# Laser_Array_Temp_Low_BRD_V2_1.net
KiCad netlist of a schematic drawn in EAGLE
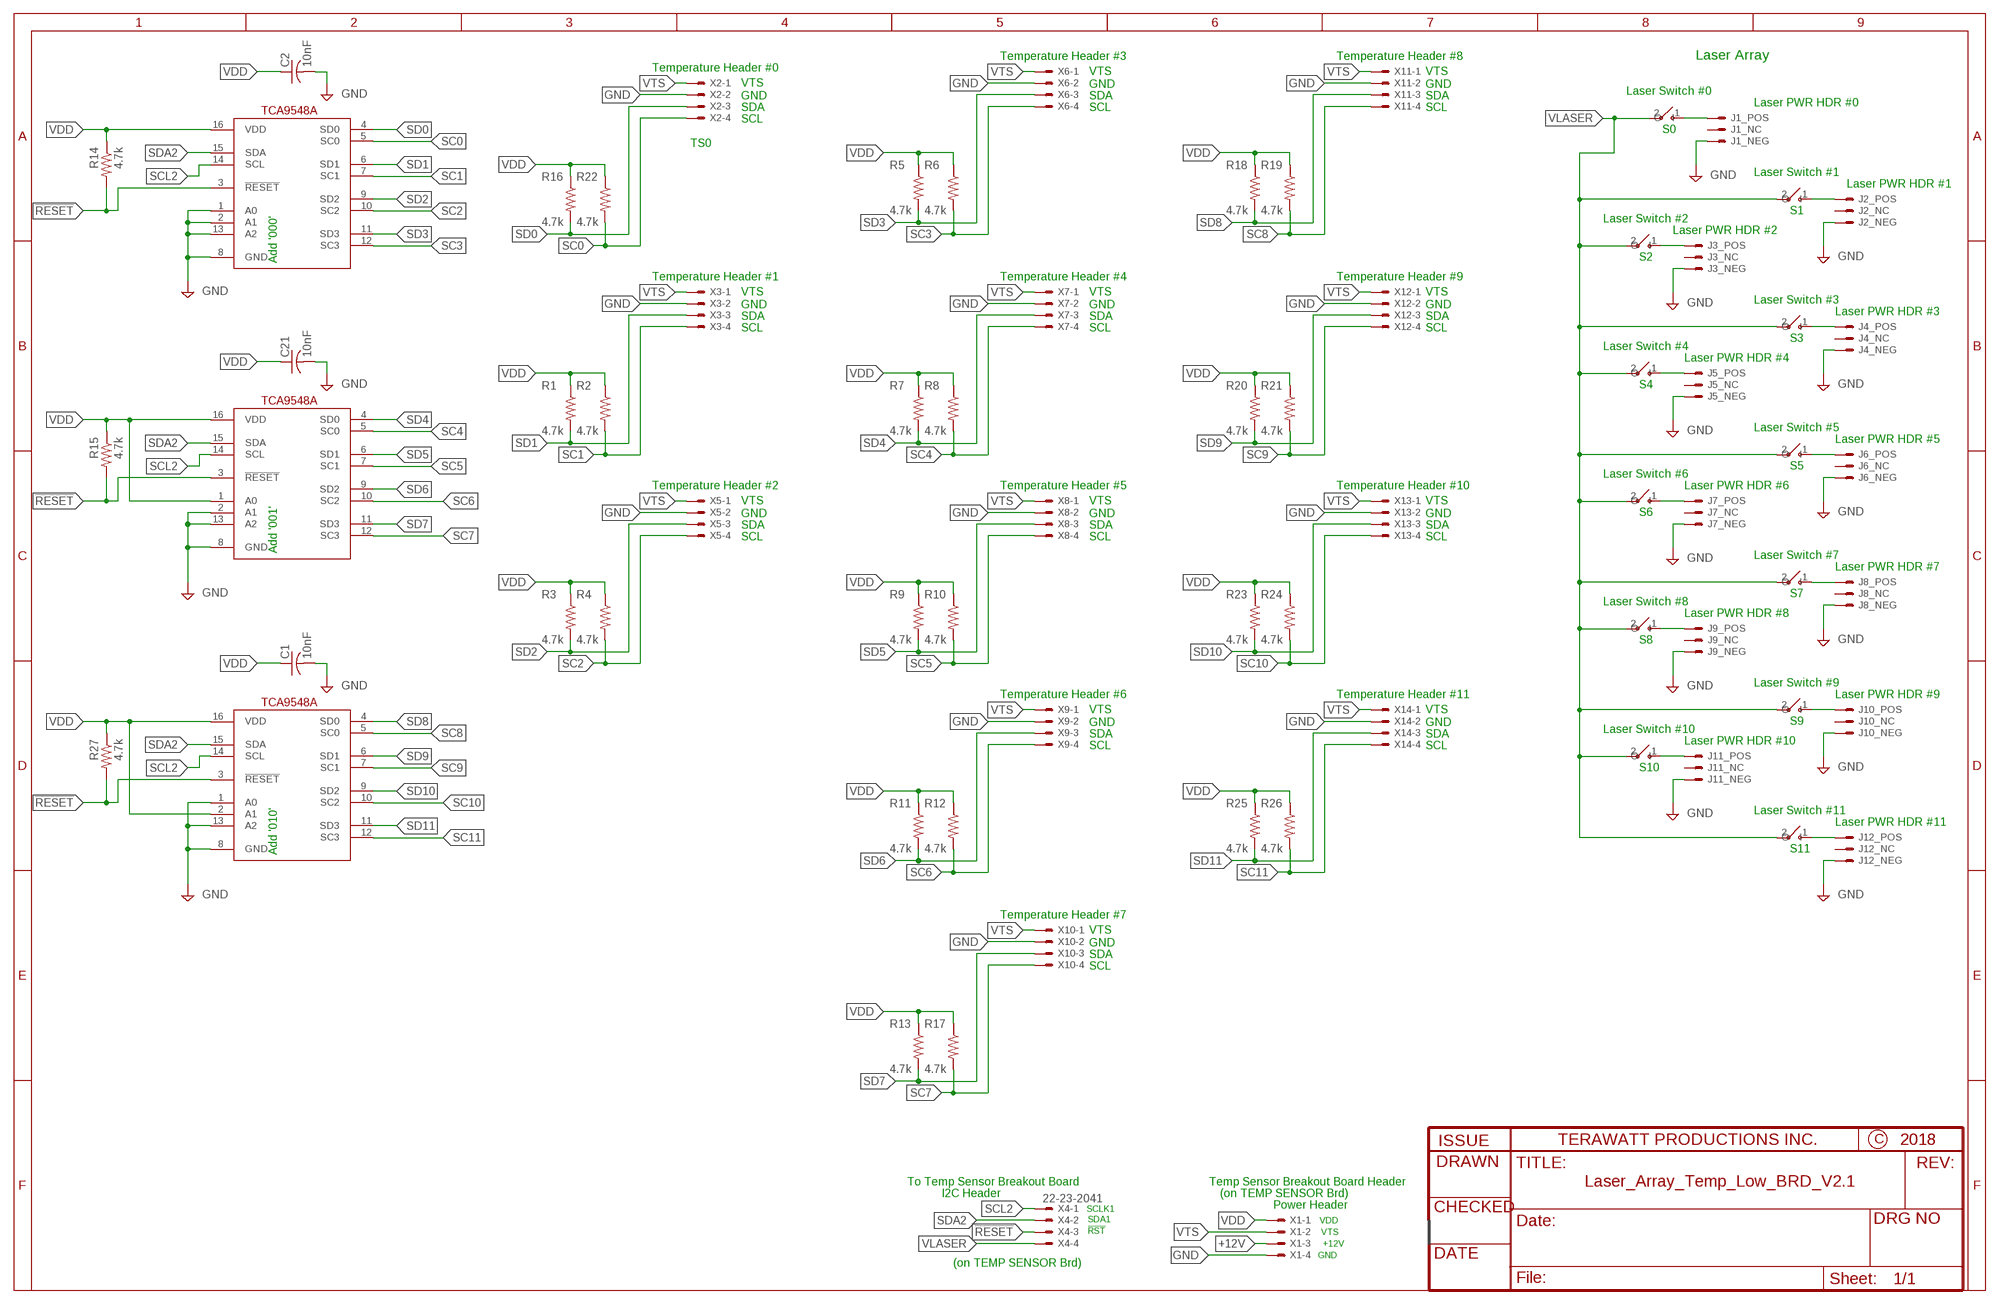
[diagram p0: schematic, sheet 1]

(export (version "E")
  (design (tool "Eeschema 10.0.6"))
  (components
    (comp (ref "C1")
      (value "10nF")
      (footprint "eagle-import:C0805")
      (libsource (lib "eagle-import") (part "C-USC0805"))
    )
    (comp (ref "C2")
      (value "10nF")
      (footprint "eagle-import:C0805")
      (libsource (lib "eagle-import") (part "C-USC0805"))
    )
    (comp (ref "C21")
      (value "10nF")
      (footprint "eagle-import:C0805")
      (libsource (lib "eagle-import") (part "C-USC0805"))
    )
    (comp (ref "J1")
      (value "LASER_MOD")
      (footprint "eagle-import:LASER_MOD")
      (libsource (lib "eagle-import") (part "LASER_MOD"))
    )
    (comp (ref "J2")
      (value "LASER_MOD")
      (footprint "eagle-import:LASER_MOD")
      (libsource (lib "eagle-import") (part "LASER_MOD"))
    )
    (comp (ref "J3")
      (value "LASER_MOD")
      (footprint "eagle-import:LASER_MOD")
      (libsource (lib "eagle-import") (part "LASER_MOD"))
    )
    (comp (ref "J4")
      (value "LASER_MOD")
      (footprint "eagle-import:LASER_MOD")
      (libsource (lib "eagle-import") (part "LASER_MOD"))
    )
    (comp (ref "J5")
      (value "LASER_MOD")
      (footprint "eagle-import:LASER_MOD")
      (libsource (lib "eagle-import") (part "LASER_MOD"))
    )
    (comp (ref "J6")
      (value "LASER_MOD")
      (footprint "eagle-import:LASER_MOD")
      (libsource (lib "eagle-import") (part "LASER_MOD"))
    )
    (comp (ref "J7")
      (value "LASER_MOD")
      (footprint "eagle-import:LASER_MOD")
      (libsource (lib "eagle-import") (part "LASER_MOD"))
    )
    (comp (ref "J8")
      (value "LASER_MOD")
      (footprint "eagle-import:LASER_MOD")
      (libsource (lib "eagle-import") (part "LASER_MOD"))
    )
    (comp (ref "J9")
      (value "LASER_MOD")
      (footprint "eagle-import:LASER_MOD")
      (libsource (lib "eagle-import") (part "LASER_MOD"))
    )
    (comp (ref "J10")
      (value "LASER_MOD")
      (footprint "eagle-import:LASER_MOD")
      (libsource (lib "eagle-import") (part "LASER_MOD"))
    )
    (comp (ref "J11")
      (value "LASER_MOD")
      (footprint "eagle-import:LASER_MOD")
      (libsource (lib "eagle-import") (part "LASER_MOD"))
    )
    (comp (ref "J12")
      (value "LASER_MOD")
      (footprint "eagle-import:LASER_MOD")
      (libsource (lib "eagle-import") (part "LASER_MOD"))
    )
    (comp (ref "R1")
      (value "4.7k")
      (footprint "eagle-import:M0805")
      (libsource (lib "eagle-import") (part "R-US_M0805"))
    )
    (comp (ref "R2")
      (value "4.7k")
      (footprint "eagle-import:M0805")
      (libsource (lib "eagle-import") (part "R-US_M0805"))
    )
    (comp (ref "R3")
      (value "4.7k")
      (footprint "eagle-import:M0805")
      (libsource (lib "eagle-import") (part "R-US_M0805"))
    )
    (comp (ref "R4")
      (value "4.7k")
      (footprint "eagle-import:M0805")
      (libsource (lib "eagle-import") (part "R-US_M0805"))
    )
    (comp (ref "R5")
      (value "4.7k")
      (footprint "eagle-import:M0805")
      (libsource (lib "eagle-import") (part "R-US_M0805"))
    )
    (comp (ref "R6")
      (value "4.7k")
      (footprint "eagle-import:M0805")
      (libsource (lib "eagle-import") (part "R-US_M0805"))
    )
    (comp (ref "R7")
      (value "4.7k")
      (footprint "eagle-import:M0805")
      (libsource (lib "eagle-import") (part "R-US_M0805"))
    )
    (comp (ref "R8")
      (value "4.7k")
      (footprint "eagle-import:M0805")
      (libsource (lib "eagle-import") (part "R-US_M0805"))
    )
    (comp (ref "R9")
      (value "4.7k")
      (footprint "eagle-import:M0805")
      (libsource (lib "eagle-import") (part "R-US_M0805"))
    )
    (comp (ref "R10")
      (value "4.7k")
      (footprint "eagle-import:M0805")
      (libsource (lib "eagle-import") (part "R-US_M0805"))
    )
    (comp (ref "R11")
      (value "4.7k")
      (footprint "eagle-import:M0805")
      (libsource (lib "eagle-import") (part "R-US_M0805"))
    )
    (comp (ref "R12")
      (value "4.7k")
      (footprint "eagle-import:M0805")
      (libsource (lib "eagle-import") (part "R-US_M0805"))
    )
    (comp (ref "R13")
      (value "4.7k")
      (footprint "eagle-import:M0805")
      (libsource (lib "eagle-import") (part "R-US_M0805"))
    )
    (comp (ref "R14")
      (value "4.7k")
      (footprint "eagle-import:M0805")
      (libsource (lib "eagle-import") (part "R-US_M0805"))
    )
    (comp (ref "R15")
      (value "4.7k")
      (footprint "eagle-import:M0805")
      (libsource (lib "eagle-import") (part "R-US_M0805"))
    )
    (comp (ref "R16")
      (value "4.7k")
      (footprint "eagle-import:M0805")
      (libsource (lib "eagle-import") (part "R-US_M0805"))
    )
    (comp (ref "R17")
      (value "4.7k")
      (footprint "eagle-import:M0805")
      (libsource (lib "eagle-import") (part "R-US_M0805"))
    )
    (comp (ref "R18")
      (value "4.7k")
      (footprint "eagle-import:M0805")
      (libsource (lib "eagle-import") (part "R-US_M0805"))
    )
    (comp (ref "R19")
      (value "4.7k")
      (footprint "eagle-import:M0805")
      (libsource (lib "eagle-import") (part "R-US_M0805"))
    )
    (comp (ref "R20")
      (value "4.7k")
      (footprint "eagle-import:M0805")
      (libsource (lib "eagle-import") (part "R-US_M0805"))
    )
    (comp (ref "R21")
      (value "4.7k")
      (footprint "eagle-import:M0805")
      (libsource (lib "eagle-import") (part "R-US_M0805"))
    )
    (comp (ref "R22")
      (value "4.7k")
      (footprint "eagle-import:M0805")
      (libsource (lib "eagle-import") (part "R-US_M0805"))
    )
    (comp (ref "R23")
      (value "4.7k")
      (footprint "eagle-import:M0805")
      (libsource (lib "eagle-import") (part "R-US_M0805"))
    )
    (comp (ref "R24")
      (value "4.7k")
      (footprint "eagle-import:M0805")
      (libsource (lib "eagle-import") (part "R-US_M0805"))
    )
    (comp (ref "R25")
      (value "4.7k")
      (footprint "eagle-import:M0805")
      (libsource (lib "eagle-import") (part "R-US_M0805"))
    )
    (comp (ref "R26")
      (value "4.7k")
      (footprint "eagle-import:M0805")
      (libsource (lib "eagle-import") (part "R-US_M0805"))
    )
    (comp (ref "R27")
      (value "4.7k")
      (footprint "eagle-import:M0805")
      (libsource (lib "eagle-import") (part "R-US_M0805"))
    )
    (comp (ref "S13")
      (value "TOGGLE_SPST")
      (footprint "eagle-import:22-23-2021")
      (libsource (lib "eagle-import") (part "TOGGLE_SPST"))
    )
    (comp (ref "S14")
      (value "TOGGLE_SPST")
      (footprint "eagle-import:22-23-2021")
      (libsource (lib "eagle-import") (part "TOGGLE_SPST"))
    )
    (comp (ref "S15")
      (value "TOGGLE_SPST")
      (footprint "eagle-import:22-23-2021")
      (libsource (lib "eagle-import") (part "TOGGLE_SPST"))
    )
    (comp (ref "S16")
      (value "TOGGLE_SPST")
      (footprint "eagle-import:22-23-2021")
      (libsource (lib "eagle-import") (part "TOGGLE_SPST"))
    )
    (comp (ref "S17")
      (value "TOGGLE_SPST")
      (footprint "eagle-import:22-23-2021")
      (libsource (lib "eagle-import") (part "TOGGLE_SPST"))
    )
    (comp (ref "S18")
      (value "TOGGLE_SPST")
      (footprint "eagle-import:22-23-2021")
      (libsource (lib "eagle-import") (part "TOGGLE_SPST"))
    )
    (comp (ref "S19")
      (value "TOGGLE_SPST")
      (footprint "eagle-import:22-23-2021")
      (libsource (lib "eagle-import") (part "TOGGLE_SPST"))
    )
    (comp (ref "S20")
      (value "TOGGLE_SPST")
      (footprint "eagle-import:22-23-2021")
      (libsource (lib "eagle-import") (part "TOGGLE_SPST"))
    )
    (comp (ref "S21")
      (value "TOGGLE_SPST")
      (footprint "eagle-import:22-23-2021")
      (libsource (lib "eagle-import") (part "TOGGLE_SPST"))
    )
    (comp (ref "S22")
      (value "TOGGLE_SPST")
      (footprint "eagle-import:22-23-2021")
      (libsource (lib "eagle-import") (part "TOGGLE_SPST"))
    )
    (comp (ref "S23")
      (value "TOGGLE_SPST")
      (footprint "eagle-import:22-23-2021")
      (libsource (lib "eagle-import") (part "TOGGLE_SPST"))
    )
    (comp (ref "S24")
      (value "TOGGLE_SPST")
      (footprint "eagle-import:22-23-2021")
      (libsource (lib "eagle-import") (part "TOGGLE_SPST"))
    )
    (comp (ref "U1")
      (value "TCA9546A")
      (footprint "eagle-import:SOIC16N")
      (libsource (lib "eagle-import") (part "TCA9546A"))
    )
    (comp (ref "U2")
      (value "TCA9546A")
      (footprint "eagle-import:SOIC16N")
      (libsource (lib "eagle-import") (part "TCA9546A"))
    )
    (comp (ref "U3")
      (value "TCA9546A")
      (footprint "eagle-import:SOIC16N")
      (libsource (lib "eagle-import") (part "TCA9546A"))
    )
    (comp (ref "X1")
      (value "22-23-2041")
      (footprint "eagle-import:22-23-2041")
      (fields (field (name "MF") "MOLEX"))
      (libsource (lib "eagle-import") (part "22-23-2041"))
    )
    (comp (ref "X2")
      (value "22-23-2041")
      (footprint "eagle-import:22-23-2041")
      (fields (field (name "MF") "MOLEX"))
      (libsource (lib "eagle-import") (part "22-23-2041"))
    )
    (comp (ref "X3")
      (value "22-23-2041")
      (footprint "eagle-import:22-23-2041")
      (fields (field (name "MF") "MOLEX"))
      (libsource (lib "eagle-import") (part "22-23-2041"))
    )
    (comp (ref "X4")
      (value "22-23-2041")
      (footprint "eagle-import:22-23-2041")
      (fields (field (name "MF") "MOLEX"))
      (libsource (lib "eagle-import") (part "22-23-2041"))
    )
    (comp (ref "X5")
      (value "22-23-2041")
      (footprint "eagle-import:22-23-2041")
      (fields (field (name "MF") "MOLEX"))
      (libsource (lib "eagle-import") (part "22-23-2041"))
    )
    (comp (ref "X6")
      (value "22-23-2041")
      (footprint "eagle-import:22-23-2041")
      (fields (field (name "MF") "MOLEX"))
      (libsource (lib "eagle-import") (part "22-23-2041"))
    )
    (comp (ref "X7")
      (value "22-23-2041")
      (footprint "eagle-import:22-23-2041")
      (fields (field (name "MF") "MOLEX"))
      (libsource (lib "eagle-import") (part "22-23-2041"))
    )
    (comp (ref "X8")
      (value "22-23-2041")
      (footprint "eagle-import:22-23-2041")
      (fields (field (name "MF") "MOLEX"))
      (libsource (lib "eagle-import") (part "22-23-2041"))
    )
    (comp (ref "X9")
      (value "22-23-2041")
      (footprint "eagle-import:22-23-2041")
      (fields (field (name "MF") "MOLEX"))
      (libsource (lib "eagle-import") (part "22-23-2041"))
    )
    (comp (ref "X10")
      (value "22-23-2041")
      (footprint "eagle-import:22-23-2041")
      (fields (field (name "MF") "MOLEX"))
      (libsource (lib "eagle-import") (part "22-23-2041"))
    )
    (comp (ref "X11")
      (value "22-23-2041")
      (footprint "eagle-import:22-23-2041")
      (fields (field (name "MF") "MOLEX"))
      (libsource (lib "eagle-import") (part "22-23-2041"))
    )
    (comp (ref "X12")
      (value "22-23-2041")
      (footprint "eagle-import:22-23-2041")
      (fields (field (name "MF") "MOLEX"))
      (libsource (lib "eagle-import") (part "22-23-2041"))
    )
    (comp (ref "X13")
      (value "22-23-2041")
      (footprint "eagle-import:22-23-2041")
      (fields (field (name "MF") "MOLEX"))
      (libsource (lib "eagle-import") (part "22-23-2041"))
    )
    (comp (ref "X14")
      (value "22-23-2041")
      (footprint "eagle-import:22-23-2041")
      (fields (field (name "MF") "MOLEX"))
      (libsource (lib "eagle-import") (part "22-23-2041"))
    )
  )
  (nets
    (net (code "1") (name "+12V") (class "Default")
      (node (ref "X1") (pin "3") (pinfunction "S_3") (pintype "passive"))
    )
    (net (code "2") (name "/~{RESET}") (class "Default")
      (node (ref "R14") (pin "2") (pinfunction "2_2") (pintype "passive"))
      (node (ref "R15") (pin "2") (pinfunction "2_2") (pintype "passive"))
      (node (ref "R27") (pin "2") (pinfunction "2_2") (pintype "passive"))
      (node (ref "U1") (pin "3") (pinfunction "~{RESET}_3") (pintype "bidirectional"))
      (node (ref "U2") (pin "3") (pinfunction "~{RESET}_3") (pintype "bidirectional"))
      (node (ref "U3") (pin "3") (pinfunction "~{RESET}_3") (pintype "bidirectional"))
      (node (ref "X4") (pin "3") (pinfunction "S_3") (pintype "passive"))
    )
    (net (code "3") (name "GND") (class "Default")
      (node (ref "C1") (pin "2") (pinfunction "2_2") (pintype "passive"))
      (node (ref "C2") (pin "2") (pinfunction "2_2") (pintype "passive"))
      (node (ref "C21") (pin "2") (pinfunction "2_2") (pintype "passive"))
      (node (ref "J1") (pin "3") (pinfunction "S_3") (pintype "passive"))
      (node (ref "J10") (pin "3") (pinfunction "S_3") (pintype "passive"))
      (node (ref "J11") (pin "3") (pinfunction "S_3") (pintype "passive"))
      (node (ref "J12") (pin "3") (pinfunction "S_3") (pintype "passive"))
      (node (ref "J2") (pin "3") (pinfunction "S_3") (pintype "passive"))
      (node (ref "J3") (pin "3") (pinfunction "S_3") (pintype "passive"))
      (node (ref "J4") (pin "3") (pinfunction "S_3") (pintype "passive"))
      (node (ref "J5") (pin "3") (pinfunction "S_3") (pintype "passive"))
      (node (ref "J6") (pin "3") (pinfunction "S_3") (pintype "passive"))
      (node (ref "J7") (pin "3") (pinfunction "S_3") (pintype "passive"))
      (node (ref "J8") (pin "3") (pinfunction "S_3") (pintype "passive"))
      (node (ref "J9") (pin "3") (pinfunction "S_3") (pintype "passive"))
      (node (ref "U1") (pin "1") (pinfunction "A0_1") (pintype "bidirectional"))
      (node (ref "U1") (pin "13") (pinfunction "A2_13") (pintype "bidirectional"))
      (node (ref "U1") (pin "2") (pinfunction "A1_2") (pintype "bidirectional"))
      (node (ref "U1") (pin "8") (pinfunction "GND_8") (pintype "bidirectional"))
      (node (ref "U2") (pin "13") (pinfunction "A2_13") (pintype "bidirectional"))
      (node (ref "U2") (pin "2") (pinfunction "A1_2") (pintype "bidirectional"))
      (node (ref "U2") (pin "8") (pinfunction "GND_8") (pintype "bidirectional"))
      (node (ref "U3") (pin "1") (pinfunction "A0_1") (pintype "bidirectional"))
      (node (ref "U3") (pin "13") (pinfunction "A2_13") (pintype "bidirectional"))
      (node (ref "U3") (pin "8") (pinfunction "GND_8") (pintype "bidirectional"))
      (node (ref "X1") (pin "4") (pinfunction "S_4") (pintype "passive"))
      (node (ref "X10") (pin "2") (pinfunction "S_2") (pintype "passive"))
      (node (ref "X11") (pin "2") (pinfunction "S_2") (pintype "passive"))
      (node (ref "X12") (pin "2") (pinfunction "S_2") (pintype "passive"))
      (node (ref "X13") (pin "2") (pinfunction "S_2") (pintype "passive"))
      (node (ref "X14") (pin "2") (pinfunction "S_2") (pintype "passive"))
      (node (ref "X2") (pin "2") (pinfunction "S_2") (pintype "passive"))
      (node (ref "X3") (pin "2") (pinfunction "S_2") (pintype "passive"))
      (node (ref "X5") (pin "2") (pinfunction "S_2") (pintype "passive"))
      (node (ref "X6") (pin "2") (pinfunction "S_2") (pintype "passive"))
      (node (ref "X7") (pin "2") (pinfunction "S_2") (pintype "passive"))
      (node (ref "X8") (pin "2") (pinfunction "S_2") (pintype "passive"))
      (node (ref "X9") (pin "2") (pinfunction "S_2") (pintype "passive"))
    )
    (net (code "4") (name "Net-(J1C-S)") (class "Default")
      (node (ref "J1") (pin "1") (pinfunction "S_1") (pintype "passive"))
      (node (ref "S16") (pin "1") (pinfunction "O_1") (pintype "bidirectional"))
    )
    (net (code "5") (name "Net-(J2C-S)") (class "Default")
      (node (ref "J2") (pin "1") (pinfunction "S_1") (pintype "passive"))
      (node (ref "S13") (pin "1") (pinfunction "O_1") (pintype "bidirectional"))
    )
    (net (code "6") (name "Net-(J3C-S)") (class "Default")
      (node (ref "J3") (pin "1") (pinfunction "S_1") (pintype "passive"))
      (node (ref "S14") (pin "1") (pinfunction "O_1") (pintype "bidirectional"))
    )
    (net (code "7") (name "Net-(J4C-S)") (class "Default")
      (node (ref "J4") (pin "1") (pinfunction "S_1") (pintype "passive"))
      (node (ref "S15") (pin "1") (pinfunction "O_1") (pintype "bidirectional"))
    )
    (net (code "8") (name "Net-(J5C-S)") (class "Default")
      (node (ref "J5") (pin "1") (pinfunction "S_1") (pintype "passive"))
      (node (ref "S17") (pin "1") (pinfunction "O_1") (pintype "bidirectional"))
    )
    (net (code "9") (name "Net-(J6C-S)") (class "Default")
      (node (ref "J6") (pin "1") (pinfunction "S_1") (pintype "passive"))
      (node (ref "S18") (pin "1") (pinfunction "O_1") (pintype "bidirectional"))
    )
    (net (code "10") (name "Net-(J7C-S)") (class "Default")
      (node (ref "J7") (pin "1") (pinfunction "S_1") (pintype "passive"))
      (node (ref "S19") (pin "1") (pinfunction "O_1") (pintype "bidirectional"))
    )
    (net (code "11") (name "Net-(J8C-S)") (class "Default")
      (node (ref "J8") (pin "1") (pinfunction "S_1") (pintype "passive"))
      (node (ref "S20") (pin "1") (pinfunction "O_1") (pintype "bidirectional"))
    )
    (net (code "12") (name "Net-(J9C-S)") (class "Default")
      (node (ref "J9") (pin "1") (pinfunction "S_1") (pintype "passive"))
      (node (ref "S21") (pin "1") (pinfunction "O_1") (pintype "bidirectional"))
    )
    (net (code "13") (name "Net-(J10C-S)") (class "Default")
      (node (ref "J10") (pin "1") (pinfunction "S_1") (pintype "passive"))
      (node (ref "S22") (pin "1") (pinfunction "O_1") (pintype "bidirectional"))
    )
    (net (code "14") (name "Net-(J11C-S)") (class "Default")
      (node (ref "J11") (pin "1") (pinfunction "S_1") (pintype "passive"))
      (node (ref "S23") (pin "1") (pinfunction "O_1") (pintype "bidirectional"))
    )
    (net (code "15") (name "Net-(J12C-S)") (class "Default")
      (node (ref "J12") (pin "1") (pinfunction "S_1") (pintype "passive"))
      (node (ref "S24") (pin "1") (pinfunction "O_1") (pintype "bidirectional"))
    )
    (net (code "16") (name "SC0") (class "Default")
      (node (ref "R22") (pin "2") (pinfunction "2_2") (pintype "passive"))
      (node (ref "U1") (pin "5") (pinfunction "SC0_5") (pintype "bidirectional"))
      (node (ref "X2") (pin "4") (pinfunction "S_4") (pintype "passive"))
    )
    (net (code "17") (name "SC1") (class "Default")
      (node (ref "R2") (pin "2") (pinfunction "2_2") (pintype "passive"))
      (node (ref "U1") (pin "7") (pinfunction "SC1_7") (pintype "bidirectional"))
      (node (ref "X3") (pin "4") (pinfunction "S_4") (pintype "passive"))
    )
    (net (code "18") (name "SC2") (class "Default")
      (node (ref "R4") (pin "2") (pinfunction "2_2") (pintype "passive"))
      (node (ref "U1") (pin "10") (pinfunction "SC2_10") (pintype "bidirectional"))
      (node (ref "X5") (pin "4") (pinfunction "S_4") (pintype "passive"))
    )
    (net (code "19") (name "SC3") (class "Default")
      (node (ref "R6") (pin "2") (pinfunction "2_2") (pintype "passive"))
      (node (ref "U1") (pin "12") (pinfunction "SC3_12") (pintype "bidirectional"))
      (node (ref "X6") (pin "4") (pinfunction "S_4") (pintype "passive"))
    )
    (net (code "20") (name "SC4") (class "Default")
      (node (ref "R8") (pin "2") (pinfunction "2_2") (pintype "passive"))
      (node (ref "U2") (pin "5") (pinfunction "SC0_5") (pintype "bidirectional"))
      (node (ref "X7") (pin "4") (pinfunction "S_4") (pintype "passive"))
    )
    (net (code "21") (name "SC5") (class "Default")
      (node (ref "R10") (pin "2") (pinfunction "2_2") (pintype "passive"))
      (node (ref "U2") (pin "7") (pinfunction "SC1_7") (pintype "bidirectional"))
      (node (ref "X8") (pin "4") (pinfunction "S_4") (pintype "passive"))
    )
    (net (code "22") (name "SC6") (class "Default")
      (node (ref "R12") (pin "2") (pinfunction "2_2") (pintype "passive"))
      (node (ref "U2") (pin "10") (pinfunction "SC2_10") (pintype "bidirectional"))
      (node (ref "X9") (pin "4") (pinfunction "S_4") (pintype "passive"))
    )
    (net (code "23") (name "SC7") (class "Default")
      (node (ref "R17") (pin "2") (pinfunction "2_2") (pintype "passive"))
      (node (ref "U2") (pin "12") (pinfunction "SC3_12") (pintype "bidirectional"))
      (node (ref "X10") (pin "4") (pinfunction "S_4") (pintype "passive"))
    )
    (net (code "24") (name "SC8") (class "Default")
      (node (ref "R19") (pin "2") (pinfunction "2_2") (pintype "passive"))
      (node (ref "U3") (pin "5") (pinfunction "SC0_5") (pintype "bidirectional"))
      (node (ref "X11") (pin "4") (pinfunction "S_4") (pintype "passive"))
    )
    (net (code "25") (name "SC9") (class "Default")
      (node (ref "R21") (pin "2") (pinfunction "2_2") (pintype "passive"))
      (node (ref "U3") (pin "7") (pinfunction "SC1_7") (pintype "bidirectional"))
      (node (ref "X12") (pin "4") (pinfunction "S_4") (pintype "passive"))
    )
    (net (code "26") (name "SC10") (class "Default")
      (node (ref "R24") (pin "2") (pinfunction "2_2") (pintype "passive"))
      (node (ref "U3") (pin "10") (pinfunction "SC2_10") (pintype "bidirectional"))
      (node (ref "X13") (pin "4") (pinfunction "S_4") (pintype "passive"))
    )
    (net (code "27") (name "SC11") (class "Default")
      (node (ref "R26") (pin "2") (pinfunction "2_2") (pintype "passive"))
      (node (ref "U3") (pin "12") (pinfunction "SC3_12") (pintype "bidirectional"))
      (node (ref "X14") (pin "4") (pinfunction "S_4") (pintype "passive"))
    )
    (net (code "28") (name "SCL2") (class "Default")
      (node (ref "U1") (pin "14") (pinfunction "SCL_14") (pintype "bidirectional"))
      (node (ref "U2") (pin "14") (pinfunction "SCL_14") (pintype "bidirectional"))
      (node (ref "U3") (pin "14") (pinfunction "SCL_14") (pintype "bidirectional"))
      (node (ref "X4") (pin "1") (pinfunction "S_1") (pintype "passive"))
    )
    (net (code "29") (name "SD0") (class "Default")
      (node (ref "R16") (pin "2") (pinfunction "2_2") (pintype "passive"))
      (node (ref "U1") (pin "4") (pinfunction "SD0_4") (pintype "bidirectional"))
      (node (ref "X2") (pin "3") (pinfunction "S_3") (pintype "passive"))
    )
    (net (code "30") (name "SD1") (class "Default")
      (node (ref "R1") (pin "2") (pinfunction "2_2") (pintype "passive"))
      (node (ref "U1") (pin "6") (pinfunction "SD1_6") (pintype "bidirectional"))
      (node (ref "X3") (pin "3") (pinfunction "S_3") (pintype "passive"))
    )
    (net (code "31") (name "SD2") (class "Default")
      (node (ref "R3") (pin "2") (pinfunction "2_2") (pintype "passive"))
      (node (ref "U1") (pin "9") (pinfunction "SD2_9") (pintype "bidirectional"))
      (node (ref "X5") (pin "3") (pinfunction "S_3") (pintype "passive"))
    )
    (net (code "32") (name "SD3") (class "Default")
      (node (ref "R5") (pin "2") (pinfunction "2_2") (pintype "passive"))
      (node (ref "U1") (pin "11") (pinfunction "SD3_11") (pintype "bidirectional"))
      (node (ref "X6") (pin "3") (pinfunction "S_3") (pintype "passive"))
    )
    (net (code "33") (name "SD4") (class "Default")
      (node (ref "R7") (pin "2") (pinfunction "2_2") (pintype "passive"))
      (node (ref "U2") (pin "4") (pinfunction "SD0_4") (pintype "bidirectional"))
      (node (ref "X7") (pin "3") (pinfunction "S_3") (pintype "passive"))
    )
    (net (code "34") (name "SD5") (class "Default")
      (node (ref "R9") (pin "2") (pinfunction "2_2") (pintype "passive"))
      (node (ref "U2") (pin "6") (pinfunction "SD1_6") (pintype "bidirectional"))
      (node (ref "X8") (pin "3") (pinfunction "S_3") (pintype "passive"))
    )
    (net (code "35") (name "SD6") (class "Default")
      (node (ref "R11") (pin "2") (pinfunction "2_2") (pintype "passive"))
      (node (ref "U2") (pin "9") (pinfunction "SD2_9") (pintype "bidirectional"))
      (node (ref "X9") (pin "3") (pinfunction "S_3") (pintype "passive"))
    )
    (net (code "36") (name "SD7") (class "Default")
      (node (ref "R13") (pin "2") (pinfunction "2_2") (pintype "passive"))
      (node (ref "U2") (pin "11") (pinfunction "SD3_11") (pintype "bidirectional"))
      (node (ref "X10") (pin "3") (pinfunction "S_3") (pintype "passive"))
    )
    (net (code "37") (name "SD8") (class "Default")
      (node (ref "R18") (pin "2") (pinfunction "2_2") (pintype "passive"))
      (node (ref "U3") (pin "4") (pinfunction "SD0_4") (pintype "bidirectional"))
      (node (ref "X11") (pin "3") (pinfunction "S_3") (pintype "passive"))
    )
    (net (code "38") (name "SD9") (class "Default")
      (node (ref "R20") (pin "2") (pinfunction "2_2") (pintype "passive"))
      (node (ref "U3") (pin "6") (pinfunction "SD1_6") (pintype "bidirectional"))
      (node (ref "X12") (pin "3") (pinfunction "S_3") (pintype "passive"))
    )
    (net (code "39") (name "SD10") (class "Default")
      (node (ref "R23") (pin "2") (pinfunction "2_2") (pintype "passive"))
      (node (ref "U3") (pin "9") (pinfunction "SD2_9") (pintype "bidirectional"))
      (node (ref "X13") (pin "3") (pinfunction "S_3") (pintype "passive"))
    )
    (net (code "40") (name "SD11") (class "Default")
      (node (ref "R25") (pin "2") (pinfunction "2_2") (pintype "passive"))
      (node (ref "U3") (pin "11") (pinfunction "SD3_11") (pintype "bidirectional"))
      (node (ref "X14") (pin "3") (pinfunction "S_3") (pintype "passive"))
    )
    (net (code "41") (name "SDA2") (class "Default")
      (node (ref "U1") (pin "15") (pinfunction "SDA_15") (pintype "bidirectional"))
      (node (ref "U2") (pin "15") (pinfunction "SDA_15") (pintype "bidirectional"))
      (node (ref "U3") (pin "15") (pinfunction "SDA_15") (pintype "bidirectional"))
      (node (ref "X4") (pin "2") (pinfunction "S_2") (pintype "passive"))
    )
    (net (code "42") (name "VDD") (class "Default")
      (node (ref "C1") (pin "1") (pinfunction "1_1") (pintype "passive"))
      (node (ref "C2") (pin "1") (pinfunction "1_1") (pintype "passive"))
      (node (ref "C21") (pin "1") (pinfunction "1_1") (pintype "passive"))
      (node (ref "R1") (pin "1") (pinfunction "1_1") (pintype "passive"))
      (node (ref "R10") (pin "1") (pinfunction "1_1") (pintype "passive"))
      (node (ref "R11") (pin "1") (pinfunction "1_1") (pintype "passive"))
      (node (ref "R12") (pin "1") (pinfunction "1_1") (pintype "passive"))
      (node (ref "R13") (pin "1") (pinfunction "1_1") (pintype "passive"))
      (node (ref "R14") (pin "1") (pinfunction "1_1") (pintype "passive"))
      (node (ref "R15") (pin "1") (pinfunction "1_1") (pintype "passive"))
      (node (ref "R16") (pin "1") (pinfunction "1_1") (pintype "passive"))
      (node (ref "R17") (pin "1") (pinfunction "1_1") (pintype "passive"))
      (node (ref "R18") (pin "1") (pinfunction "1_1") (pintype "passive"))
      (node (ref "R19") (pin "1") (pinfunction "1_1") (pintype "passive"))
      (node (ref "R2") (pin "1") (pinfunction "1_1") (pintype "passive"))
      (node (ref "R20") (pin "1") (pinfunction "1_1") (pintype "passive"))
      (node (ref "R21") (pin "1") (pinfunction "1_1") (pintype "passive"))
      (node (ref "R22") (pin "1") (pinfunction "1_1") (pintype "passive"))
      (node (ref "R23") (pin "1") (pinfunction "1_1") (pintype "passive"))
      (node (ref "R24") (pin "1") (pinfunction "1_1") (pintype "passive"))
      (node (ref "R25") (pin "1") (pinfunction "1_1") (pintype "passive"))
      (node (ref "R26") (pin "1") (pinfunction "1_1") (pintype "passive"))
      (node (ref "R27") (pin "1") (pinfunction "1_1") (pintype "passive"))
      (node (ref "R3") (pin "1") (pinfunction "1_1") (pintype "passive"))
      (node (ref "R4") (pin "1") (pinfunction "1_1") (pintype "passive"))
      (node (ref "R5") (pin "1") (pinfunction "1_1") (pintype "passive"))
      (node (ref "R6") (pin "1") (pinfunction "1_1") (pintype "passive"))
      (node (ref "R7") (pin "1") (pinfunction "1_1") (pintype "passive"))
      (node (ref "R8") (pin "1") (pinfunction "1_1") (pintype "passive"))
      (node (ref "R9") (pin "1") (pinfunction "1_1") (pintype "passive"))
      (node (ref "U1") (pin "16") (pinfunction "VDD_16") (pintype "bidirectional"))
      (node (ref "U2") (pin "1") (pinfunction "A0_1") (pintype "bidirectional"))
      (node (ref "U2") (pin "16") (pinfunction "VDD_16") (pintype "bidirectional"))
      (node (ref "U3") (pin "16") (pinfunction "VDD_16") (pintype "bidirectional"))
      (node (ref "U3") (pin "2") (pinfunction "A1_2") (pintype "bidirectional"))
      (node (ref "X1") (pin "1") (pinfunction "S_1") (pintype "passive"))
    )
    (net (code "43") (name "VLASER") (class "Default")
      (node (ref "S13") (pin "2") (pinfunction "I_2") (pintype "bidirectional"))
      (node (ref "S14") (pin "2") (pinfunction "I_2") (pintype "bidirectional"))
      (node (ref "S15") (pin "2") (pinfunction "I_2") (pintype "bidirectional"))
      (node (ref "S16") (pin "2") (pinfunction "I_2") (pintype "bidirectional"))
      (node (ref "S17") (pin "2") (pinfunction "I_2") (pintype "bidirectional"))
      (node (ref "S18") (pin "2") (pinfunction "I_2") (pintype "bidirectional"))
      (node (ref "S19") (pin "2") (pinfunction "I_2") (pintype "bidirectional"))
      (node (ref "S20") (pin "2") (pinfunction "I_2") (pintype "bidirectional"))
      (node (ref "S21") (pin "2") (pinfunction "I_2") (pintype "bidirectional"))
      (node (ref "S22") (pin "2") (pinfunction "I_2") (pintype "bidirectional"))
      (node (ref "S23") (pin "2") (pinfunction "I_2") (pintype "bidirectional"))
      (node (ref "S24") (pin "2") (pinfunction "I_2") (pintype "bidirectional"))
      (node (ref "X4") (pin "4") (pinfunction "S_4") (pintype "passive"))
    )
    (net (code "44") (name "VTS") (class "Default")
      (node (ref "X1") (pin "2") (pinfunction "S_2") (pintype "passive"))
      (node (ref "X10") (pin "1") (pinfunction "S_1") (pintype "passive"))
      (node (ref "X11") (pin "1") (pinfunction "S_1") (pintype "passive"))
      (node (ref "X12") (pin "1") (pinfunction "S_1") (pintype "passive"))
      (node (ref "X13") (pin "1") (pinfunction "S_1") (pintype "passive"))
      (node (ref "X14") (pin "1") (pinfunction "S_1") (pintype "passive"))
      (node (ref "X2") (pin "1") (pinfunction "S_1") (pintype "passive"))
      (node (ref "X3") (pin "1") (pinfunction "S_1") (pintype "passive"))
      (node (ref "X5") (pin "1") (pinfunction "S_1") (pintype "passive"))
      (node (ref "X6") (pin "1") (pinfunction "S_1") (pintype "passive"))
      (node (ref "X7") (pin "1") (pinfunction "S_1") (pintype "passive"))
      (node (ref "X8") (pin "1") (pinfunction "S_1") (pintype "passive"))
      (node (ref "X9") (pin "1") (pinfunction "S_1") (pintype "passive"))
    )
    (net (code "45") (name "unconnected-(J1A-S-Pad2)") (class "Default")
      (node (ref "J1") (pin "2") (pinfunction "S_2") (pintype "passive"))
    )
    (net (code "46") (name "unconnected-(J2A-S-Pad2)") (class "Default")
      (node (ref "J2") (pin "2") (pinfunction "S_2") (pintype "passive"))
    )
    (net (code "47") (name "unconnected-(J3A-S-Pad2)") (class "Default")
      (node (ref "J3") (pin "2") (pinfunction "S_2") (pintype "passive"))
    )
    (net (code "48") (name "unconnected-(J4A-S-Pad2)") (class "Default")
      (node (ref "J4") (pin "2") (pinfunction "S_2") (pintype "passive"))
    )
    (net (code "49") (name "unconnected-(J5A-S-Pad2)") (class "Default")
      (node (ref "J5") (pin "2") (pinfunction "S_2") (pintype "passive"))
    )
    (net (code "50") (name "unconnected-(J6A-S-Pad2)") (class "Default")
      (node (ref "J6") (pin "2") (pinfunction "S_2") (pintype "passive"))
    )
    (net (code "51") (name "unconnected-(J7A-S-Pad2)") (class "Default")
      (node (ref "J7") (pin "2") (pinfunction "S_2") (pintype "passive"))
    )
    (net (code "52") (name "unconnected-(J8A-S-Pad2)") (class "Default")
      (node (ref "J8") (pin "2") (pinfunction "S_2") (pintype "passive"))
    )
    (net (code "53") (name "unconnected-(J9A-S-Pad2)") (class "Default")
      (node (ref "J9") (pin "2") (pinfunction "S_2") (pintype "passive"))
    )
    (net (code "54") (name "unconnected-(J10A-S-Pad2)") (class "Default")
      (node (ref "J10") (pin "2") (pinfunction "S_2") (pintype "passive"))
    )
    (net (code "55") (name "unconnected-(J11A-S-Pad2)") (class "Default")
      (node (ref "J11") (pin "2") (pinfunction "S_2") (pintype "passive"))
    )
    (net (code "56") (name "unconnected-(J12A-S-Pad2)") (class "Default")
      (node (ref "J12") (pin "2") (pinfunction "S_2") (pintype "passive"))
    )
  )
)
